# 18-Led7.net
KiCad netlist of a schematic drawn in Altium Designer
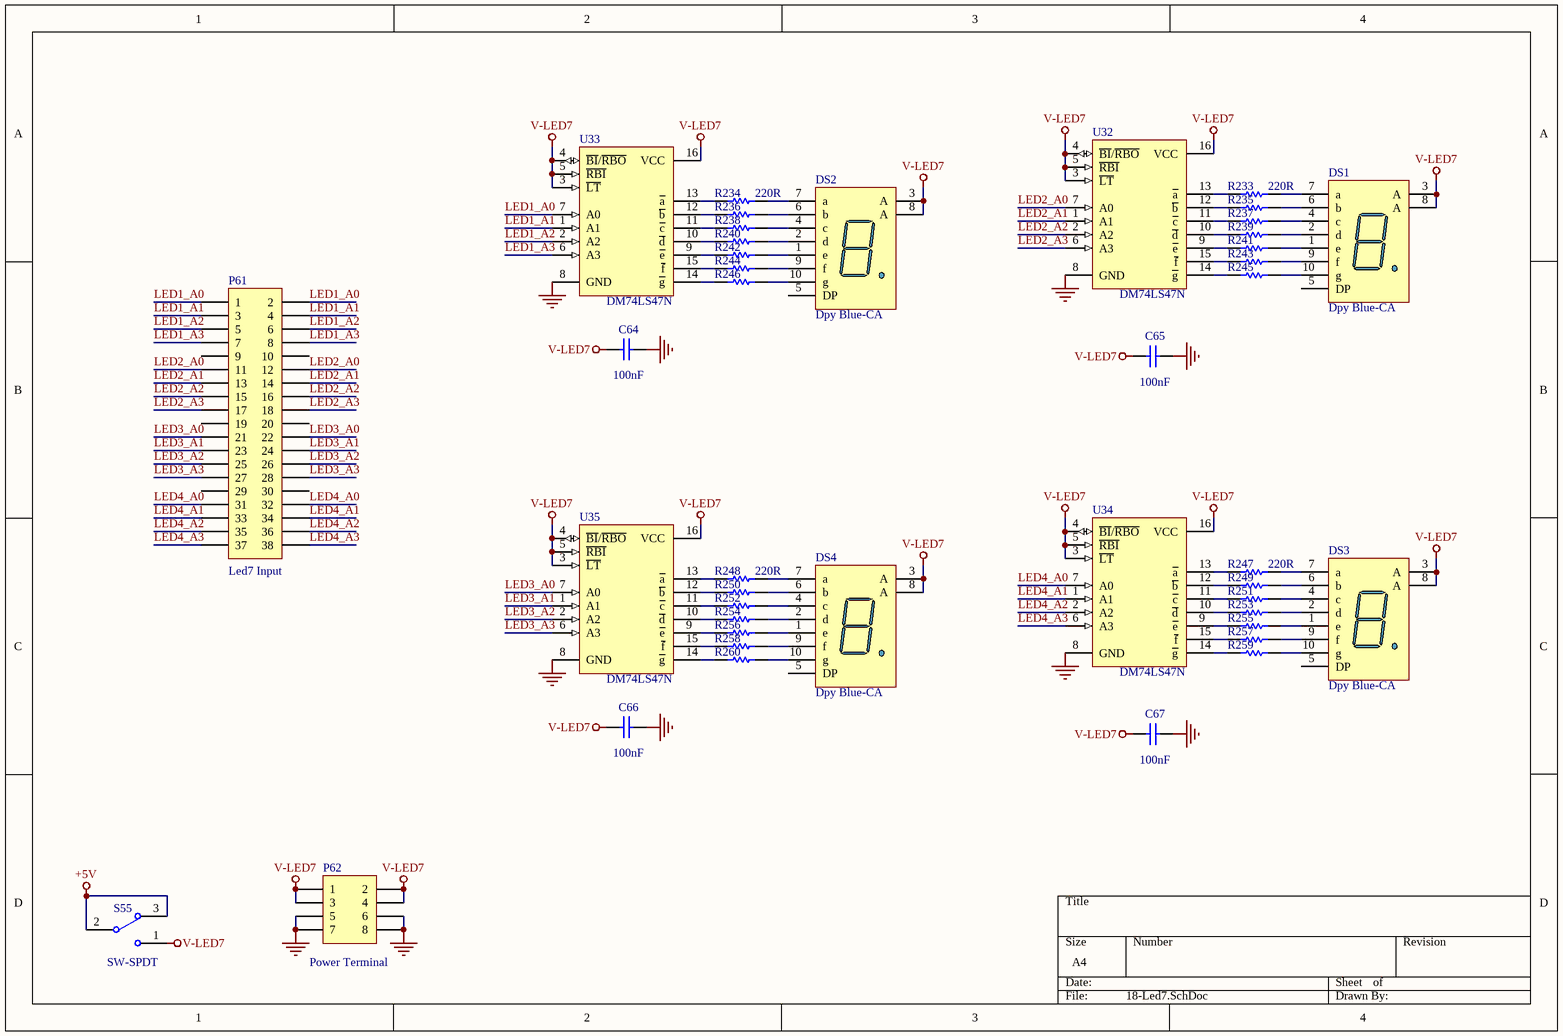
[diagram p0: 18-Led7.SchDoc]

(export (version "E")
  (design (tool "Eeschema 10.0.6"))
  (components
    (comp (ref "C64")
      (value "100nF")
      (footprint "c-0805")
      (description "Capacitor")
      (fields (field (name "Comment") "104") (field (name "PUBLISHER") "Altium Limited"))
      (libsource (lib "Miscellaneous Devices") (part "Cap"))
    )
    (comp (ref "C65")
      (value "100nF")
      (footprint "c-0805")
      (description "Capacitor")
      (fields (field (name "Comment") "104") (field (name "PUBLISHER") "Altium Limited"))
      (libsource (lib "Miscellaneous Devices") (part "Cap"))
    )
    (comp (ref "C66")
      (value "100nF")
      (footprint "c-0805")
      (description "Capacitor")
      (fields (field (name "Comment") "104") (field (name "PUBLISHER") "Altium Limited"))
      (libsource (lib "Miscellaneous Devices") (part "Cap"))
    )
    (comp (ref "C67")
      (value "100nF")
      (footprint "c-0805")
      (description "Capacitor")
      (fields (field (name "Comment") "104") (field (name "PUBLISHER") "Altium Limited"))
      (libsource (lib "Miscellaneous Devices") (part "Cap"))
    )
    (comp (ref "DS1")
      (value "Dpy Blue-CA")
      (footprint "LED7SEG-1-0.56")
      (description "14.2 mm General Purpose Blue 7-Segment Display: CA, RH DP, Gray Surface")
      (fields (field (name "PUBLISHER") "Altium Limited"))
      (libsource (lib "Miscellaneous Devices") (part "Dpy Blue-CA"))
    )
    (comp (ref "DS2")
      (value "Dpy Blue-CA")
      (footprint "LED7SEG-1-0.56")
      (description "14.2 mm General Purpose Blue 7-Segment Display: CA, RH DP, Gray Surface")
      (fields (field (name "PUBLISHER") "Altium Limited"))
      (libsource (lib "Miscellaneous Devices") (part "Dpy Blue-CA"))
    )
    (comp (ref "DS3")
      (value "Dpy Blue-CA")
      (footprint "LED7SEG-1-0.56")
      (description "14.2 mm General Purpose Blue 7-Segment Display: CA, RH DP, Gray Surface")
      (fields (field (name "PUBLISHER") "Altium Limited"))
      (libsource (lib "Miscellaneous Devices") (part "Dpy Blue-CA"))
    )
    (comp (ref "DS4")
      (value "Dpy Blue-CA")
      (footprint "LED7SEG-1-0.56")
      (description "14.2 mm General Purpose Blue 7-Segment Display: CA, RH DP, Gray Surface")
      (fields (field (name "PUBLISHER") "Altium Limited"))
      (libsource (lib "Miscellaneous Devices") (part "Dpy Blue-CA"))
    )
    (comp (ref "P61")
      (value "Led7 Input")
      (footprint "HDR2X19")
      (description "Header, 19-Pin, Dual row")
      (fields (field (name "Comment") "Header 19X2"))
      (libsource (lib "Miscellaneous Connectors") (part "Header 19X2"))
    )
    (comp (ref "P62")
      (value "Header 4X2")
      (footprint "HDR2X4")
      (description "Header, 4-Pin, Dual row")
      (fields (field (name "PUBLISHER") "Power Terminal"))
      (libsource (lib "Miscellaneous Connectors") (part "Header 4X2"))
    )
    (comp (ref "R233")
      (value "220R")
      (footprint "r-0805")
      (description "Resistor")
      (fields (field (name "PUBLISHER") "Altium Limited"))
      (libsource (lib "Miscellaneous Devices") (part "Res1"))
    )
    (comp (ref "R234")
      (value "220R")
      (footprint "r-0805")
      (description "Resistor")
      (fields (field (name "PUBLISHER") "Altium Limited"))
      (libsource (lib "Miscellaneous Devices") (part "Res1"))
    )
    (comp (ref "R235")
      (value "220R")
      (footprint "r-0805")
      (description "Resistor")
      (fields (field (name "PUBLISHER") "Altium Limited"))
      (libsource (lib "Miscellaneous Devices") (part "Res1"))
    )
    (comp (ref "R236")
      (value "220R")
      (footprint "r-0805")
      (description "Resistor")
      (fields (field (name "PUBLISHER") "Altium Limited"))
      (libsource (lib "Miscellaneous Devices") (part "Res1"))
    )
    (comp (ref "R237")
      (value "220R")
      (footprint "r-0805")
      (description "Resistor")
      (fields (field (name "PUBLISHER") "Altium Limited"))
      (libsource (lib "Miscellaneous Devices") (part "Res1"))
    )
    (comp (ref "R238")
      (value "220R")
      (footprint "r-0805")
      (description "Resistor")
      (fields (field (name "PUBLISHER") "Altium Limited"))
      (libsource (lib "Miscellaneous Devices") (part "Res1"))
    )
    (comp (ref "R239")
      (value "220R")
      (footprint "r-0805")
      (description "Resistor")
      (fields (field (name "PUBLISHER") "Altium Limited"))
      (libsource (lib "Miscellaneous Devices") (part "Res1"))
    )
    (comp (ref "R240")
      (value "220R")
      (footprint "r-0805")
      (description "Resistor")
      (fields (field (name "PUBLISHER") "Altium Limited"))
      (libsource (lib "Miscellaneous Devices") (part "Res1"))
    )
    (comp (ref "R241")
      (value "220R")
      (footprint "r-0805")
      (description "Resistor")
      (fields (field (name "PUBLISHER") "Altium Limited"))
      (libsource (lib "Miscellaneous Devices") (part "Res1"))
    )
    (comp (ref "R242")
      (value "220R")
      (footprint "r-0805")
      (description "Resistor")
      (fields (field (name "PUBLISHER") "Altium Limited"))
      (libsource (lib "Miscellaneous Devices") (part "Res1"))
    )
    (comp (ref "R243")
      (value "220R")
      (footprint "r-0805")
      (description "Resistor")
      (fields (field (name "PUBLISHER") "Altium Limited"))
      (libsource (lib "Miscellaneous Devices") (part "Res1"))
    )
    (comp (ref "R244")
      (value "220R")
      (footprint "r-0805")
      (description "Resistor")
      (fields (field (name "PUBLISHER") "Altium Limited"))
      (libsource (lib "Miscellaneous Devices") (part "Res1"))
    )
    (comp (ref "R245")
      (value "220R")
      (footprint "r-0805")
      (description "Resistor")
      (fields (field (name "PUBLISHER") "Altium Limited"))
      (libsource (lib "Miscellaneous Devices") (part "Res1"))
    )
    (comp (ref "R246")
      (value "220R")
      (footprint "r-0805")
      (description "Resistor")
      (fields (field (name "PUBLISHER") "Altium Limited"))
      (libsource (lib "Miscellaneous Devices") (part "Res1"))
    )
    (comp (ref "R247")
      (value "220R")
      (footprint "r-0805")
      (description "Resistor")
      (fields (field (name "PUBLISHER") "Altium Limited"))
      (libsource (lib "Miscellaneous Devices") (part "Res1"))
    )
    (comp (ref "R248")
      (value "220R")
      (footprint "r-0805")
      (description "Resistor")
      (fields (field (name "PUBLISHER") "Altium Limited"))
      (libsource (lib "Miscellaneous Devices") (part "Res1"))
    )
    (comp (ref "R249")
      (value "220R")
      (footprint "r-0805")
      (description "Resistor")
      (fields (field (name "PUBLISHER") "Altium Limited"))
      (libsource (lib "Miscellaneous Devices") (part "Res1"))
    )
    (comp (ref "R250")
      (value "220R")
      (footprint "r-0805")
      (description "Resistor")
      (fields (field (name "PUBLISHER") "Altium Limited"))
      (libsource (lib "Miscellaneous Devices") (part "Res1"))
    )
    (comp (ref "R251")
      (value "220R")
      (footprint "r-0805")
      (description "Resistor")
      (fields (field (name "PUBLISHER") "Altium Limited"))
      (libsource (lib "Miscellaneous Devices") (part "Res1"))
    )
    (comp (ref "R252")
      (value "220R")
      (footprint "r-0805")
      (description "Resistor")
      (fields (field (name "PUBLISHER") "Altium Limited"))
      (libsource (lib "Miscellaneous Devices") (part "Res1"))
    )
    (comp (ref "R253")
      (value "220R")
      (footprint "r-0805")
      (description "Resistor")
      (fields (field (name "PUBLISHER") "Altium Limited"))
      (libsource (lib "Miscellaneous Devices") (part "Res1"))
    )
    (comp (ref "R254")
      (value "220R")
      (footprint "r-0805")
      (description "Resistor")
      (fields (field (name "PUBLISHER") "Altium Limited"))
      (libsource (lib "Miscellaneous Devices") (part "Res1"))
    )
    (comp (ref "R255")
      (value "220R")
      (footprint "r-0805")
      (description "Resistor")
      (fields (field (name "PUBLISHER") "Altium Limited"))
      (libsource (lib "Miscellaneous Devices") (part "Res1"))
    )
    (comp (ref "R256")
      (value "220R")
      (footprint "r-0805")
      (description "Resistor")
      (fields (field (name "PUBLISHER") "Altium Limited"))
      (libsource (lib "Miscellaneous Devices") (part "Res1"))
    )
    (comp (ref "R257")
      (value "220R")
      (footprint "r-0805")
      (description "Resistor")
      (fields (field (name "PUBLISHER") "Altium Limited"))
      (libsource (lib "Miscellaneous Devices") (part "Res1"))
    )
    (comp (ref "R258")
      (value "220R")
      (footprint "r-0805")
      (description "Resistor")
      (fields (field (name "PUBLISHER") "Altium Limited"))
      (libsource (lib "Miscellaneous Devices") (part "Res1"))
    )
    (comp (ref "R259")
      (value "220R")
      (footprint "r-0805")
      (description "Resistor")
      (fields (field (name "PUBLISHER") "Altium Limited"))
      (libsource (lib "Miscellaneous Devices") (part "Res1"))
    )
    (comp (ref "R260")
      (value "220R")
      (footprint "r-0805")
      (description "Resistor")
      (fields (field (name "PUBLISHER") "Altium Limited"))
      (libsource (lib "Miscellaneous Devices") (part "Res1"))
    )
    (comp (ref "S55")
      (value "SW-SPDT")
      (footprint "sW-DIP1SMD")
      (description "SPDT Subminiature Toggle Switch, Right Angle Mounting, Vertical Actuation")
      (fields (field (name "PUBLISHER") "Altium Limited"))
      (libsource (lib "Miscellaneous Devices") (part "SW-SPDT"))
    )
    (comp (ref "U32")
      (value "DM74LS47N")
      (footprint "DIP16/W0.3")
      (description "BCD to 7-Segment Decoder/Driver with Open-Collector Output")
      (fields (field (name "PUBLISHER") "Altium Limited"))
      (libsource (lib "FSC Interface Display Driver") (part "DM74LS47N"))
    )
    (comp (ref "U33")
      (value "DM74LS47N")
      (footprint "DIP16/W0.3")
      (description "BCD to 7-Segment Decoder/Driver with Open-Collector Output")
      (fields (field (name "PUBLISHER") "Altium Limited"))
      (libsource (lib "FSC Interface Display Driver") (part "DM74LS47N"))
    )
    (comp (ref "U34")
      (value "DM74LS47N")
      (footprint "DIP16/W0.3")
      (description "BCD to 7-Segment Decoder/Driver with Open-Collector Output")
      (fields (field (name "PUBLISHER") "Altium Limited"))
      (libsource (lib "FSC Interface Display Driver") (part "DM74LS47N"))
    )
    (comp (ref "U35")
      (value "DM74LS47N")
      (footprint "DIP16/W0.3")
      (description "BCD to 7-Segment Decoder/Driver with Open-Collector Output")
      (fields (field (name "PUBLISHER") "Altium Limited"))
      (libsource (lib "FSC Interface Display Driver") (part "DM74LS47N"))
    )
  )
  (nets
    (net (code "1") (name "+5V") (class "Default")
      (node (ref "S55") (pin "2") (pinfunction "2_2") (pintype "passive"))
      (node (ref "S55") (pin "3") (pinfunction "3_3") (pintype "passive"))
    )
    (net (code "2") (name "/LED1_A0") (class "Default")
      (node (ref "P61") (pin "1") (pinfunction "1_1") (pintype "passive"))
      (node (ref "P61") (pin "2") (pinfunction "2_2") (pintype "passive"))
      (node (ref "U33") (pin "7") (pinfunction "A0_7") (pintype "input"))
    )
    (net (code "3") (name "/LED1_A1") (class "Default")
      (node (ref "P61") (pin "3") (pinfunction "3_3") (pintype "passive"))
      (node (ref "P61") (pin "4") (pinfunction "4_4") (pintype "passive"))
      (node (ref "U33") (pin "1") (pinfunction "A1_1") (pintype "input"))
    )
    (net (code "4") (name "/LED1_A2") (class "Default")
      (node (ref "P61") (pin "5") (pinfunction "5_5") (pintype "passive"))
      (node (ref "P61") (pin "6") (pinfunction "6_6") (pintype "passive"))
      (node (ref "U33") (pin "2") (pinfunction "A2_2") (pintype "input"))
    )
    (net (code "5") (name "/LED1_A3") (class "Default")
      (node (ref "P61") (pin "7") (pinfunction "7_7") (pintype "passive"))
      (node (ref "P61") (pin "8") (pinfunction "8_8") (pintype "passive"))
      (node (ref "U33") (pin "6") (pinfunction "A3_6") (pintype "input"))
    )
    (net (code "6") (name "/LED2_A0") (class "Default")
      (node (ref "P61") (pin "11") (pinfunction "11_11") (pintype "passive"))
      (node (ref "P61") (pin "12") (pinfunction "12_12") (pintype "passive"))
      (node (ref "U32") (pin "7") (pinfunction "A0_7") (pintype "input"))
    )
    (net (code "7") (name "/LED2_A1") (class "Default")
      (node (ref "P61") (pin "13") (pinfunction "13_13") (pintype "passive"))
      (node (ref "P61") (pin "14") (pinfunction "14_14") (pintype "passive"))
      (node (ref "U32") (pin "1") (pinfunction "A1_1") (pintype "input"))
    )
    (net (code "8") (name "/LED2_A2") (class "Default")
      (node (ref "P61") (pin "15") (pinfunction "15_15") (pintype "passive"))
      (node (ref "P61") (pin "16") (pinfunction "16_16") (pintype "passive"))
      (node (ref "U32") (pin "2") (pinfunction "A2_2") (pintype "input"))
    )
    (net (code "9") (name "/LED2_A3") (class "Default")
      (node (ref "P61") (pin "17") (pinfunction "17_17") (pintype "passive"))
      (node (ref "P61") (pin "18") (pinfunction "18_18") (pintype "passive"))
      (node (ref "U32") (pin "6") (pinfunction "A3_6") (pintype "input"))
    )
    (net (code "10") (name "/LED3_A0") (class "Default")
      (node (ref "P61") (pin "21") (pinfunction "21_21") (pintype "passive"))
      (node (ref "P61") (pin "22") (pinfunction "22_22") (pintype "passive"))
      (node (ref "U35") (pin "7") (pinfunction "A0_7") (pintype "input"))
    )
    (net (code "11") (name "/LED3_A1") (class "Default")
      (node (ref "P61") (pin "23") (pinfunction "23_23") (pintype "passive"))
      (node (ref "P61") (pin "24") (pinfunction "24_24") (pintype "passive"))
      (node (ref "U35") (pin "1") (pinfunction "A1_1") (pintype "input"))
    )
    (net (code "12") (name "/LED3_A2") (class "Default")
      (node (ref "P61") (pin "25") (pinfunction "25_25") (pintype "passive"))
      (node (ref "P61") (pin "26") (pinfunction "26_26") (pintype "passive"))
      (node (ref "U35") (pin "2") (pinfunction "A2_2") (pintype "input"))
    )
    (net (code "13") (name "/LED3_A3") (class "Default")
      (node (ref "P61") (pin "27") (pinfunction "27_27") (pintype "passive"))
      (node (ref "P61") (pin "28") (pinfunction "28_28") (pintype "passive"))
      (node (ref "U35") (pin "6") (pinfunction "A3_6") (pintype "input"))
    )
    (net (code "14") (name "/LED4_A0") (class "Default")
      (node (ref "P61") (pin "31") (pinfunction "31_31") (pintype "passive"))
      (node (ref "P61") (pin "32") (pinfunction "32_32") (pintype "passive"))
      (node (ref "U34") (pin "7") (pinfunction "A0_7") (pintype "input"))
    )
    (net (code "15") (name "/LED4_A1") (class "Default")
      (node (ref "P61") (pin "33") (pinfunction "33_33") (pintype "passive"))
      (node (ref "P61") (pin "34") (pinfunction "34_34") (pintype "passive"))
      (node (ref "U34") (pin "1") (pinfunction "A1_1") (pintype "input"))
    )
    (net (code "16") (name "/LED4_A2") (class "Default")
      (node (ref "P61") (pin "35") (pinfunction "35_35") (pintype "passive"))
      (node (ref "P61") (pin "36") (pinfunction "36_36") (pintype "passive"))
      (node (ref "U34") (pin "2") (pinfunction "A2_2") (pintype "input"))
    )
    (net (code "17") (name "/LED4_A3") (class "Default")
      (node (ref "P61") (pin "37") (pinfunction "37_37") (pintype "passive"))
      (node (ref "P61") (pin "38") (pinfunction "38_38") (pintype "passive"))
      (node (ref "U34") (pin "6") (pinfunction "A3_6") (pintype "input"))
    )
    (net (code "18") (name "GND") (class "Default")
      (node (ref "C64") (pin "2") (pinfunction "2_2") (pintype "passive"))
      (node (ref "C65") (pin "2") (pinfunction "2_2") (pintype "passive"))
      (node (ref "C66") (pin "2") (pinfunction "2_2") (pintype "passive"))
      (node (ref "C67") (pin "2") (pinfunction "2_2") (pintype "passive"))
      (node (ref "P62") (pin "5") (pinfunction "5_5") (pintype "passive"))
      (node (ref "P62") (pin "6") (pinfunction "6_6") (pintype "passive"))
      (node (ref "P62") (pin "7") (pinfunction "7_7") (pintype "passive"))
      (node (ref "P62") (pin "8") (pinfunction "8_8") (pintype "passive"))
      (node (ref "U32") (pin "8") (pinfunction "GND_8") (pintype "power_in"))
      (node (ref "U33") (pin "8") (pinfunction "GND_8") (pintype "power_in"))
      (node (ref "U34") (pin "8") (pinfunction "GND_8") (pintype "power_in"))
      (node (ref "U35") (pin "8") (pinfunction "GND_8") (pintype "power_in"))
    )
    (net (code "19") (name "Net-(DS1-a)") (class "Default")
      (node (ref "DS1") (pin "7") (pinfunction "a_7") (pintype "passive"))
      (node (ref "R233") (pin "2") (pinfunction "2_2") (pintype "passive"))
    )
    (net (code "20") (name "Net-(DS1-b)") (class "Default")
      (node (ref "DS1") (pin "6") (pinfunction "b_6") (pintype "passive"))
      (node (ref "R235") (pin "2") (pinfunction "2_2") (pintype "passive"))
    )
    (net (code "21") (name "Net-(DS1-c)") (class "Default")
      (node (ref "DS1") (pin "4") (pinfunction "c_4") (pintype "passive"))
      (node (ref "R237") (pin "2") (pinfunction "2_2") (pintype "passive"))
    )
    (net (code "22") (name "Net-(DS1-d)") (class "Default")
      (node (ref "DS1") (pin "2") (pinfunction "d_2") (pintype "passive"))
      (node (ref "R239") (pin "2") (pinfunction "2_2") (pintype "passive"))
    )
    (net (code "23") (name "Net-(DS1-e)") (class "Default")
      (node (ref "DS1") (pin "1") (pinfunction "e_1") (pintype "passive"))
      (node (ref "R241") (pin "2") (pinfunction "2_2") (pintype "passive"))
    )
    (net (code "24") (name "Net-(DS1-f)") (class "Default")
      (node (ref "DS1") (pin "9") (pinfunction "f_9") (pintype "passive"))
      (node (ref "R243") (pin "2") (pinfunction "2_2") (pintype "passive"))
    )
    (net (code "25") (name "Net-(DS1-g)") (class "Default")
      (node (ref "DS1") (pin "10") (pinfunction "g_10") (pintype "passive"))
      (node (ref "R245") (pin "2") (pinfunction "2_2") (pintype "passive"))
    )
    (net (code "26") (name "Net-(DS2-a)") (class "Default")
      (node (ref "DS2") (pin "7") (pinfunction "a_7") (pintype "passive"))
      (node (ref "R234") (pin "2") (pinfunction "2_2") (pintype "passive"))
    )
    (net (code "27") (name "Net-(DS2-b)") (class "Default")
      (node (ref "DS2") (pin "6") (pinfunction "b_6") (pintype "passive"))
      (node (ref "R236") (pin "2") (pinfunction "2_2") (pintype "passive"))
    )
    (net (code "28") (name "Net-(DS2-c)") (class "Default")
      (node (ref "DS2") (pin "4") (pinfunction "c_4") (pintype "passive"))
      (node (ref "R238") (pin "2") (pinfunction "2_2") (pintype "passive"))
    )
    (net (code "29") (name "Net-(DS2-d)") (class "Default")
      (node (ref "DS2") (pin "2") (pinfunction "d_2") (pintype "passive"))
      (node (ref "R240") (pin "2") (pinfunction "2_2") (pintype "passive"))
    )
    (net (code "30") (name "Net-(DS2-e)") (class "Default")
      (node (ref "DS2") (pin "1") (pinfunction "e_1") (pintype "passive"))
      (node (ref "R242") (pin "2") (pinfunction "2_2") (pintype "passive"))
    )
    (net (code "31") (name "Net-(DS2-f)") (class "Default")
      (node (ref "DS2") (pin "9") (pinfunction "f_9") (pintype "passive"))
      (node (ref "R244") (pin "2") (pinfunction "2_2") (pintype "passive"))
    )
    (net (code "32") (name "Net-(DS2-g)") (class "Default")
      (node (ref "DS2") (pin "10") (pinfunction "g_10") (pintype "passive"))
      (node (ref "R246") (pin "2") (pinfunction "2_2") (pintype "passive"))
    )
    (net (code "33") (name "Net-(DS3-a)") (class "Default")
      (node (ref "DS3") (pin "7") (pinfunction "a_7") (pintype "passive"))
      (node (ref "R247") (pin "2") (pinfunction "2_2") (pintype "passive"))
    )
    (net (code "34") (name "Net-(DS3-b)") (class "Default")
      (node (ref "DS3") (pin "6") (pinfunction "b_6") (pintype "passive"))
      (node (ref "R249") (pin "2") (pinfunction "2_2") (pintype "passive"))
    )
    (net (code "35") (name "Net-(DS3-c)") (class "Default")
      (node (ref "DS3") (pin "4") (pinfunction "c_4") (pintype "passive"))
      (node (ref "R251") (pin "2") (pinfunction "2_2") (pintype "passive"))
    )
    (net (code "36") (name "Net-(DS3-d)") (class "Default")
      (node (ref "DS3") (pin "2") (pinfunction "d_2") (pintype "passive"))
      (node (ref "R253") (pin "2") (pinfunction "2_2") (pintype "passive"))
    )
    (net (code "37") (name "Net-(DS3-e)") (class "Default")
      (node (ref "DS3") (pin "1") (pinfunction "e_1") (pintype "passive"))
      (node (ref "R255") (pin "2") (pinfunction "2_2") (pintype "passive"))
    )
    (net (code "38") (name "Net-(DS3-f)") (class "Default")
      (node (ref "DS3") (pin "9") (pinfunction "f_9") (pintype "passive"))
      (node (ref "R257") (pin "2") (pinfunction "2_2") (pintype "passive"))
    )
    (net (code "39") (name "Net-(DS3-g)") (class "Default")
      (node (ref "DS3") (pin "10") (pinfunction "g_10") (pintype "passive"))
      (node (ref "R259") (pin "2") (pinfunction "2_2") (pintype "passive"))
    )
    (net (code "40") (name "Net-(DS4-a)") (class "Default")
      (node (ref "DS4") (pin "7") (pinfunction "a_7") (pintype "passive"))
      (node (ref "R248") (pin "2") (pinfunction "2_2") (pintype "passive"))
    )
    (net (code "41") (name "Net-(DS4-b)") (class "Default")
      (node (ref "DS4") (pin "6") (pinfunction "b_6") (pintype "passive"))
      (node (ref "R250") (pin "2") (pinfunction "2_2") (pintype "passive"))
    )
    (net (code "42") (name "Net-(DS4-c)") (class "Default")
      (node (ref "DS4") (pin "4") (pinfunction "c_4") (pintype "passive"))
      (node (ref "R252") (pin "2") (pinfunction "2_2") (pintype "passive"))
    )
    (net (code "43") (name "Net-(DS4-d)") (class "Default")
      (node (ref "DS4") (pin "2") (pinfunction "d_2") (pintype "passive"))
      (node (ref "R254") (pin "2") (pinfunction "2_2") (pintype "passive"))
    )
    (net (code "44") (name "Net-(DS4-e)") (class "Default")
      (node (ref "DS4") (pin "1") (pinfunction "e_1") (pintype "passive"))
      (node (ref "R256") (pin "2") (pinfunction "2_2") (pintype "passive"))
    )
    (net (code "45") (name "Net-(DS4-f)") (class "Default")
      (node (ref "DS4") (pin "9") (pinfunction "f_9") (pintype "passive"))
      (node (ref "R258") (pin "2") (pinfunction "2_2") (pintype "passive"))
    )
    (net (code "46") (name "Net-(DS4-g)") (class "Default")
      (node (ref "DS4") (pin "10") (pinfunction "g_10") (pintype "passive"))
      (node (ref "R260") (pin "2") (pinfunction "2_2") (pintype "passive"))
    )
    (net (code "47") (name "Net-(U32-~{a})") (class "Default")
      (node (ref "R233") (pin "1") (pinfunction "1_1") (pintype "passive"))
      (node (ref "U32") (pin "13") (pinfunction "~{a}_13") (pintype "open_collector"))
    )
    (net (code "48") (name "Net-(U32-~{b})") (class "Default")
      (node (ref "R235") (pin "1") (pinfunction "1_1") (pintype "passive"))
      (node (ref "U32") (pin "12") (pinfunction "~{b}_12") (pintype "open_collector"))
    )
    (net (code "49") (name "Net-(U32-~{c})") (class "Default")
      (node (ref "R237") (pin "1") (pinfunction "1_1") (pintype "passive"))
      (node (ref "U32") (pin "11") (pinfunction "~{c}_11") (pintype "open_collector"))
    )
    (net (code "50") (name "Net-(U32-~{d})") (class "Default")
      (node (ref "R239") (pin "1") (pinfunction "1_1") (pintype "passive"))
      (node (ref "U32") (pin "10") (pinfunction "~{d}_10") (pintype "open_collector"))
    )
    (net (code "51") (name "Net-(U32-~{e})") (class "Default")
      (node (ref "R241") (pin "1") (pinfunction "1_1") (pintype "passive"))
      (node (ref "U32") (pin "9") (pinfunction "~{e}_9") (pintype "open_collector"))
    )
    (net (code "52") (name "Net-(U32-~{f})") (class "Default")
      (node (ref "R243") (pin "1") (pinfunction "1_1") (pintype "passive"))
      (node (ref "U32") (pin "15") (pinfunction "~{f}_15") (pintype "open_collector"))
    )
    (net (code "53") (name "Net-(U32-~{g})") (class "Default")
      (node (ref "R245") (pin "1") (pinfunction "1_1") (pintype "passive"))
      (node (ref "U32") (pin "14") (pinfunction "~{g}_14") (pintype "open_collector"))
    )
    (net (code "54") (name "Net-(U33-~{a})") (class "Default")
      (node (ref "R234") (pin "1") (pinfunction "1_1") (pintype "passive"))
      (node (ref "U33") (pin "13") (pinfunction "~{a}_13") (pintype "open_collector"))
    )
    (net (code "55") (name "Net-(U33-~{b})") (class "Default")
      (node (ref "R236") (pin "1") (pinfunction "1_1") (pintype "passive"))
      (node (ref "U33") (pin "12") (pinfunction "~{b}_12") (pintype "open_collector"))
    )
    (net (code "56") (name "Net-(U33-~{c})") (class "Default")
      (node (ref "R238") (pin "1") (pinfunction "1_1") (pintype "passive"))
      (node (ref "U33") (pin "11") (pinfunction "~{c}_11") (pintype "open_collector"))
    )
    (net (code "57") (name "Net-(U33-~{d})") (class "Default")
      (node (ref "R240") (pin "1") (pinfunction "1_1") (pintype "passive"))
      (node (ref "U33") (pin "10") (pinfunction "~{d}_10") (pintype "open_collector"))
    )
    (net (code "58") (name "Net-(U33-~{e})") (class "Default")
      (node (ref "R242") (pin "1") (pinfunction "1_1") (pintype "passive"))
      (node (ref "U33") (pin "9") (pinfunction "~{e}_9") (pintype "open_collector"))
    )
    (net (code "59") (name "Net-(U33-~{f})") (class "Default")
      (node (ref "R244") (pin "1") (pinfunction "1_1") (pintype "passive"))
      (node (ref "U33") (pin "15") (pinfunction "~{f}_15") (pintype "open_collector"))
    )
    (net (code "60") (name "Net-(U33-~{g})") (class "Default")
      (node (ref "R246") (pin "1") (pinfunction "1_1") (pintype "passive"))
      (node (ref "U33") (pin "14") (pinfunction "~{g}_14") (pintype "open_collector"))
    )
    (net (code "61") (name "Net-(U34-~{a})") (class "Default")
      (node (ref "R247") (pin "1") (pinfunction "1_1") (pintype "passive"))
      (node (ref "U34") (pin "13") (pinfunction "~{a}_13") (pintype "open_collector"))
    )
    (net (code "62") (name "Net-(U34-~{b})") (class "Default")
      (node (ref "R249") (pin "1") (pinfunction "1_1") (pintype "passive"))
      (node (ref "U34") (pin "12") (pinfunction "~{b}_12") (pintype "open_collector"))
    )
    (net (code "63") (name "Net-(U34-~{c})") (class "Default")
      (node (ref "R251") (pin "1") (pinfunction "1_1") (pintype "passive"))
      (node (ref "U34") (pin "11") (pinfunction "~{c}_11") (pintype "open_collector"))
    )
    (net (code "64") (name "Net-(U34-~{d})") (class "Default")
      (node (ref "R253") (pin "1") (pinfunction "1_1") (pintype "passive"))
      (node (ref "U34") (pin "10") (pinfunction "~{d}_10") (pintype "open_collector"))
    )
    (net (code "65") (name "Net-(U34-~{e})") (class "Default")
      (node (ref "R255") (pin "1") (pinfunction "1_1") (pintype "passive"))
      (node (ref "U34") (pin "9") (pinfunction "~{e}_9") (pintype "open_collector"))
    )
    (net (code "66") (name "Net-(U34-~{f})") (class "Default")
      (node (ref "R257") (pin "1") (pinfunction "1_1") (pintype "passive"))
      (node (ref "U34") (pin "15") (pinfunction "~{f}_15") (pintype "open_collector"))
    )
    (net (code "67") (name "Net-(U34-~{g})") (class "Default")
      (node (ref "R259") (pin "1") (pinfunction "1_1") (pintype "passive"))
      (node (ref "U34") (pin "14") (pinfunction "~{g}_14") (pintype "open_collector"))
    )
    (net (code "68") (name "Net-(U35-~{a})") (class "Default")
      (node (ref "R248") (pin "1") (pinfunction "1_1") (pintype "passive"))
      (node (ref "U35") (pin "13") (pinfunction "~{a}_13") (pintype "open_collector"))
    )
    (net (code "69") (name "Net-(U35-~{b})") (class "Default")
      (node (ref "R250") (pin "1") (pinfunction "1_1") (pintype "passive"))
      (node (ref "U35") (pin "12") (pinfunction "~{b}_12") (pintype "open_collector"))
    )
    (net (code "70") (name "Net-(U35-~{c})") (class "Default")
      (node (ref "R252") (pin "1") (pinfunction "1_1") (pintype "passive"))
      (node (ref "U35") (pin "11") (pinfunction "~{c}_11") (pintype "open_collector"))
    )
    (net (code "71") (name "Net-(U35-~{d})") (class "Default")
      (node (ref "R254") (pin "1") (pinfunction "1_1") (pintype "passive"))
      (node (ref "U35") (pin "10") (pinfunction "~{d}_10") (pintype "open_collector"))
    )
    (net (code "72") (name "Net-(U35-~{e})") (class "Default")
      (node (ref "R256") (pin "1") (pinfunction "1_1") (pintype "passive"))
      (node (ref "U35") (pin "9") (pinfunction "~{e}_9") (pintype "open_collector"))
    )
    (net (code "73") (name "Net-(U35-~{f})") (class "Default")
      (node (ref "R258") (pin "1") (pinfunction "1_1") (pintype "passive"))
      (node (ref "U35") (pin "15") (pinfunction "~{f}_15") (pintype "open_collector"))
    )
    (net (code "74") (name "Net-(U35-~{g})") (class "Default")
      (node (ref "R260") (pin "1") (pinfunction "1_1") (pintype "passive"))
      (node (ref "U35") (pin "14") (pinfunction "~{g}_14") (pintype "open_collector"))
    )
    (net (code "75") (name "V-LED7") (class "Default")
      (node (ref "C64") (pin "1") (pinfunction "1_1") (pintype "passive"))
      (node (ref "C65") (pin "1") (pinfunction "1_1") (pintype "passive"))
      (node (ref "C66") (pin "1") (pinfunction "1_1") (pintype "passive"))
      (node (ref "C67") (pin "1") (pinfunction "1_1") (pintype "passive"))
      (node (ref "DS1") (pin "3") (pinfunction "A_3") (pintype "passive"))
      (node (ref "DS1") (pin "8") (pinfunction "A_8") (pintype "passive"))
      (node (ref "DS2") (pin "3") (pinfunction "A_3") (pintype "passive"))
      (node (ref "DS2") (pin "8") (pinfunction "A_8") (pintype "passive"))
      (node (ref "DS3") (pin "3") (pinfunction "A_3") (pintype "passive"))
      (node (ref "DS3") (pin "8") (pinfunction "A_8") (pintype "passive"))
      (node (ref "DS4") (pin "3") (pinfunction "A_3") (pintype "passive"))
      (node (ref "DS4") (pin "8") (pinfunction "A_8") (pintype "passive"))
      (node (ref "P62") (pin "1") (pinfunction "1_1") (pintype "passive"))
      (node (ref "P62") (pin "2") (pinfunction "2_2") (pintype "passive"))
      (node (ref "P62") (pin "3") (pinfunction "3_3") (pintype "passive"))
      (node (ref "P62") (pin "4") (pinfunction "4_4") (pintype "passive"))
      (node (ref "S55") (pin "1") (pinfunction "1_1") (pintype "passive"))
      (node (ref "U32") (pin "16") (pinfunction "VCC_16") (pintype "power_in"))
      (node (ref "U32") (pin "3") (pinfunction "~{LT}_3") (pintype "input"))
      (node (ref "U32") (pin "4") (pinfunction "~{BI}/~{RBO}_4") (pintype "bidirectional"))
      (node (ref "U32") (pin "5") (pinfunction "~{RBI}_5") (pintype "input"))
      (node (ref "U33") (pin "16") (pinfunction "VCC_16") (pintype "power_in"))
      (node (ref "U33") (pin "3") (pinfunction "~{LT}_3") (pintype "input"))
      (node (ref "U33") (pin "4") (pinfunction "~{BI}/~{RBO}_4") (pintype "bidirectional"))
      (node (ref "U33") (pin "5") (pinfunction "~{RBI}_5") (pintype "input"))
      (node (ref "U34") (pin "16") (pinfunction "VCC_16") (pintype "power_in"))
      (node (ref "U34") (pin "3") (pinfunction "~{LT}_3") (pintype "input"))
      (node (ref "U34") (pin "4") (pinfunction "~{BI}/~{RBO}_4") (pintype "bidirectional"))
      (node (ref "U34") (pin "5") (pinfunction "~{RBI}_5") (pintype "input"))
      (node (ref "U35") (pin "16") (pinfunction "VCC_16") (pintype "power_in"))
      (node (ref "U35") (pin "3") (pinfunction "~{LT}_3") (pintype "input"))
      (node (ref "U35") (pin "4") (pinfunction "~{BI}/~{RBO}_4") (pintype "bidirectional"))
      (node (ref "U35") (pin "5") (pinfunction "~{RBI}_5") (pintype "input"))
    )
    (net (code "76") (name "unconnected-(DS1-DP-Pad5)") (class "Default")
      (node (ref "DS1") (pin "5") (pinfunction "DP_5") (pintype "passive"))
    )
    (net (code "77") (name "unconnected-(DS2-DP-Pad5)") (class "Default")
      (node (ref "DS2") (pin "5") (pinfunction "DP_5") (pintype "passive"))
    )
    (net (code "78") (name "unconnected-(DS3-DP-Pad5)") (class "Default")
      (node (ref "DS3") (pin "5") (pinfunction "DP_5") (pintype "passive"))
    )
    (net (code "79") (name "unconnected-(DS4-DP-Pad5)") (class "Default")
      (node (ref "DS4") (pin "5") (pinfunction "DP_5") (pintype "passive"))
    )
    (net (code "80") (name "unconnected-(P61-Pad9)") (class "Default")
      (node (ref "P61") (pin "9") (pinfunction "9_9") (pintype "passive"))
    )
    (net (code "81") (name "unconnected-(P61-Pad10)") (class "Default")
      (node (ref "P61") (pin "10") (pinfunction "10_10") (pintype "passive"))
    )
    (net (code "82") (name "unconnected-(P61-Pad19)") (class "Default")
      (node (ref "P61") (pin "19") (pinfunction "19_19") (pintype "passive"))
    )
    (net (code "83") (name "unconnected-(P61-Pad20)") (class "Default")
      (node (ref "P61") (pin "20") (pinfunction "20_20") (pintype "passive"))
    )
    (net (code "84") (name "unconnected-(P61-Pad29)") (class "Default")
      (node (ref "P61") (pin "29") (pinfunction "29_29") (pintype "passive"))
    )
    (net (code "85") (name "unconnected-(P61-Pad30)") (class "Default")
      (node (ref "P61") (pin "30") (pinfunction "30_30") (pintype "passive"))
    )
  )
)
